# Main.net
KiCad netlist of a schematic drawn in Altium Designer
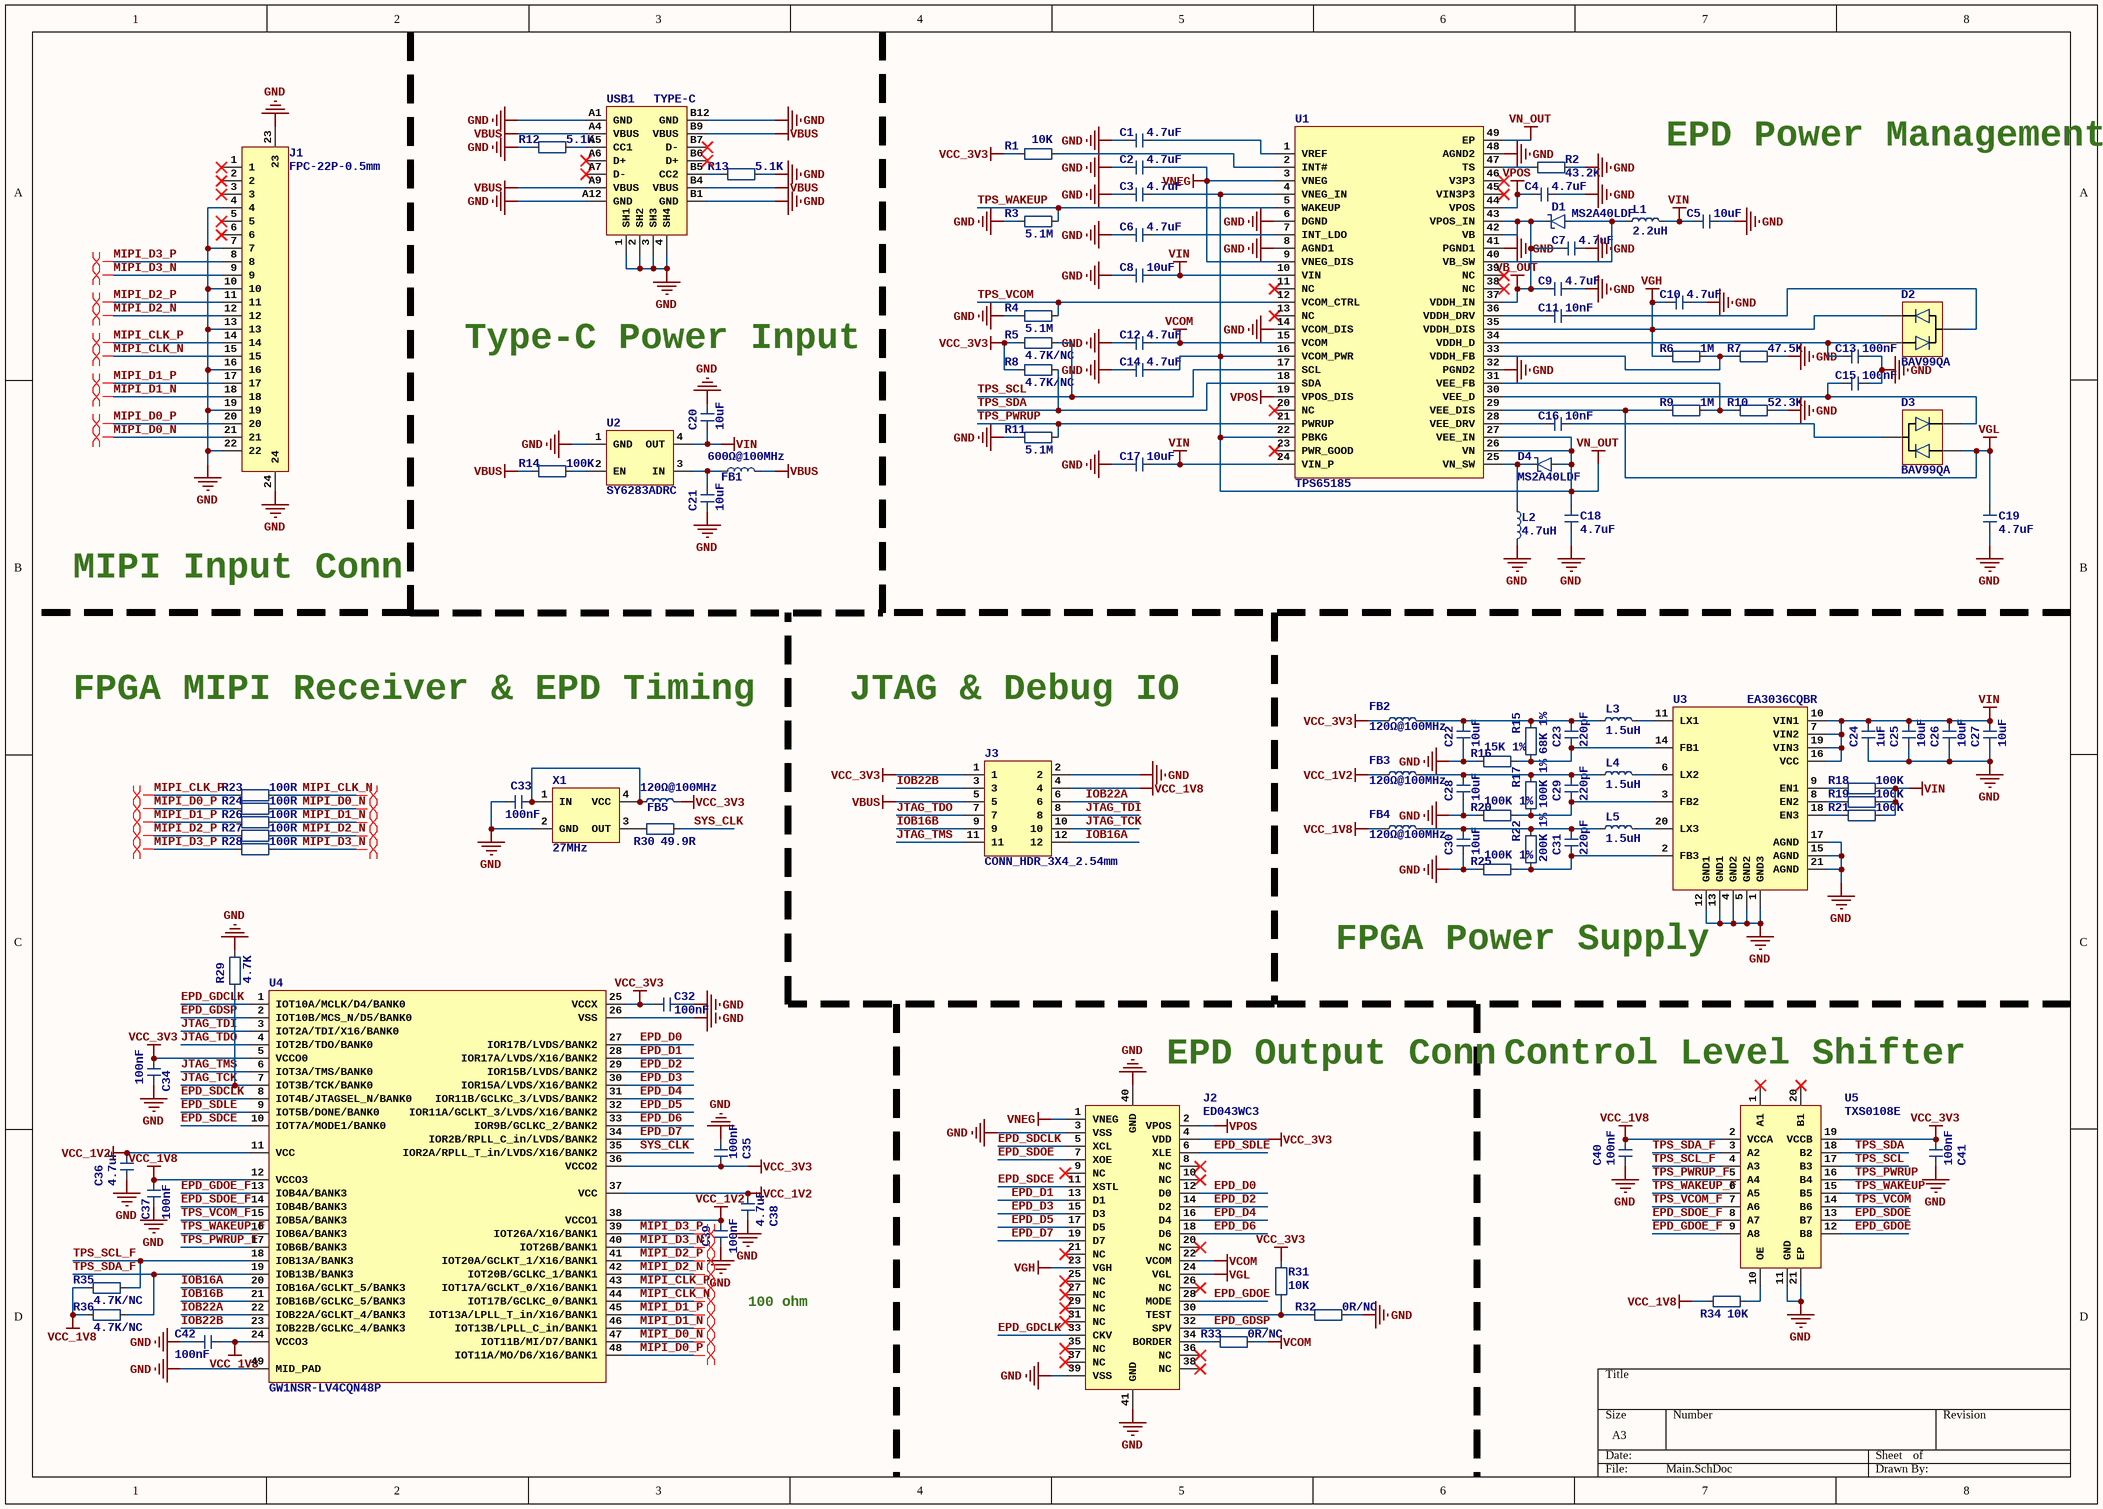
[diagram p0: Main.SchDoc]

(export (version "E")
  (design (tool "Eeschema 10.0.6"))
  (components
    (comp (ref "C1")
      (value "4.7uF")
      (footprint "Capacitor-0402")
      (description "CL05A475MO5NUNC")
      (libsource (lib "mLib") (part "Capacitor-0402"))
    )
    (comp (ref "C2")
      (value "4.7uF")
      (footprint "Capacitor-0805")
      (description "CL21A475KBQNNNE")
      (libsource (lib "mLib") (part "Capacitor-0805"))
    )
    (comp (ref "C3")
      (value "4.7uF")
      (footprint "Capacitor-0805")
      (description "CL21A475KBQNNNE")
      (libsource (lib "mLib") (part "Capacitor-0805"))
    )
    (comp (ref "C4")
      (value "4.7uF")
      (footprint "Capacitor-0805")
      (description "CL21A475KBQNNNE")
      (libsource (lib "mLib") (part "Capacitor-0805"))
    )
    (comp (ref "C5")
      (value "10uF")
      (footprint "Capacitor-0603")
      (description "CL10A106KP8NNNC")
      (libsource (lib "mLib") (part "Capacitor-0603"))
    )
    (comp (ref "C6")
      (value "4.7uF")
      (footprint "Capacitor-0402")
      (description "CL05A475MO5NUNC")
      (libsource (lib "mLib") (part "Capacitor-0402"))
    )
    (comp (ref "C7")
      (value "4.7uF")
      (footprint "Capacitor-0805")
      (description "CL21A475KBQNNNE")
      (libsource (lib "mLib") (part "Capacitor-0805"))
    )
    (comp (ref "C8")
      (value "10uF")
      (footprint "Capacitor-0603")
      (description "CL10A106KP8NNNC")
      (libsource (lib "mLib") (part "Capacitor-0603"))
    )
    (comp (ref "C9")
      (value "4.7uF")
      (footprint "Capacitor-0805")
      (description "CL21A475KBQNNNE")
      (libsource (lib "mLib") (part "Capacitor-0805"))
    )
    (comp (ref "C10")
      (value "4.7uF")
      (footprint "Capacitor-0805")
      (description "CL21A475KBQNNNE")
      (libsource (lib "mLib") (part "Capacitor-0805"))
    )
    (comp (ref "C11")
      (value "10nF")
      (footprint "Capacitor-0402")
      (description "CL05B103KB5NNNC")
      (libsource (lib "mLib") (part "Capacitor-0402"))
    )
    (comp (ref "C12")
      (value "4.7uF")
      (footprint "Capacitor-0402")
      (description "CL05A475MO5NUNC")
      (libsource (lib "mLib") (part "Capacitor-0402"))
    )
    (comp (ref "C13")
      (value "100nF")
      (footprint "Capacitor-0402")
      (description "0402B104K500NT")
      (libsource (lib "mLib") (part "Capacitor-0402"))
    )
    (comp (ref "C14")
      (value "4.7uF")
      (footprint "Capacitor-0805")
      (description "CL21A475KBQNNNE")
      (libsource (lib "mLib") (part "Capacitor-0805"))
    )
    (comp (ref "C15")
      (value "100nF")
      (footprint "Capacitor-0402")
      (description "0402B104K500NT")
      (libsource (lib "mLib") (part "Capacitor-0402"))
    )
    (comp (ref "C16")
      (value "10nF")
      (footprint "Capacitor-0402")
      (description "CL05B103KB5NNNC")
      (libsource (lib "mLib") (part "Capacitor-0402"))
    )
    (comp (ref "C17")
      (value "10uF")
      (footprint "Capacitor-0603")
      (description "CL10A106KP8NNNC")
      (libsource (lib "mLib") (part "Capacitor-0603"))
    )
    (comp (ref "C18")
      (value "4.7uF")
      (footprint "Capacitor-0805")
      (description "CL21A475KBQNNNE")
      (libsource (lib "mLib") (part "Capacitor-0805"))
    )
    (comp (ref "C19")
      (value "4.7uF")
      (footprint "Capacitor-0805")
      (description "CL21A475KBQNNNE")
      (libsource (lib "mLib") (part "Capacitor-0805"))
    )
    (comp (ref "C20")
      (value "10uF")
      (footprint "Capacitor-0402")
      (description "HGC0402R5106M100NTEJ")
      (libsource (lib "mLib") (part "Capacitor-0402"))
    )
    (comp (ref "C21")
      (value "10uF")
      (footprint "Capacitor-0402")
      (description "HGC0402R5106M100NTEJ")
      (libsource (lib "mLib") (part "Capacitor-0402"))
    )
    (comp (ref "C22")
      (value "10uF")
      (footprint "Capacitor-0402")
      (description "HGC0402R5106M100NTEJ")
      (libsource (lib "mLib") (part "Capacitor-0402"))
    )
    (comp (ref "C23")
      (value "220pF")
      (footprint "Capacitor-0402")
      (description "CL05C221JB5NNNC")
      (libsource (lib "mLib") (part "Capacitor-0402"))
    )
    (comp (ref "C24")
      (value "1uF")
      (footprint "Capacitor-0402")
      (description "CL05A105KO5NNNC")
      (libsource (lib "mLib") (part "Capacitor-0402"))
    )
    (comp (ref "C25")
      (value "10uF")
      (footprint "Capacitor-0402")
      (description "HGC0402R5106M100NTEJ")
      (libsource (lib "mLib") (part "Capacitor-0402"))
    )
    (comp (ref "C26")
      (value "10uF")
      (footprint "Capacitor-0402")
      (description "HGC0402R5106M100NTEJ")
      (libsource (lib "mLib") (part "Capacitor-0402"))
    )
    (comp (ref "C27")
      (value "10uF")
      (footprint "Capacitor-0402")
      (description "HGC0402R5106M100NTEJ")
      (libsource (lib "mLib") (part "Capacitor-0402"))
    )
    (comp (ref "C28")
      (value "10uF")
      (footprint "Capacitor-0402")
      (description "HGC0402R5106M100NTEJ")
      (libsource (lib "mLib") (part "Capacitor-0402"))
    )
    (comp (ref "C29")
      (value "220pF")
      (footprint "Capacitor-0402")
      (description "CL05C221JB5NNNC")
      (libsource (lib "mLib") (part "Capacitor-0402"))
    )
    (comp (ref "C30")
      (value "10uF")
      (footprint "Capacitor-0402")
      (description "HGC0402R5106M100NTEJ")
      (libsource (lib "mLib") (part "Capacitor-0402"))
    )
    (comp (ref "C31")
      (value "220pF")
      (footprint "Capacitor-0402")
      (description "CL05C221JB5NNNC")
      (libsource (lib "mLib") (part "Capacitor-0402"))
    )
    (comp (ref "C32")
      (value "100nF")
      (footprint "Capacitor-0402")
      (description "100nF/X5R/25V")
      (libsource (lib "mLib") (part "Capacitor-0402"))
    )
    (comp (ref "C33")
      (value "100nF")
      (footprint "Capacitor-0402")
      (description "100nF/X5R/25V")
      (libsource (lib "mLib") (part "Capacitor-0402"))
    )
    (comp (ref "C34")
      (value "100nF")
      (footprint "Capacitor-0402")
      (description "100nF/X5R/25V")
      (libsource (lib "mLib") (part "Capacitor-0402"))
    )
    (comp (ref "C35")
      (value "100nF")
      (footprint "Capacitor-0402")
      (description "100nF/X5R/25V")
      (libsource (lib "mLib") (part "Capacitor-0402"))
    )
    (comp (ref "C36")
      (value "4.7uF")
      (footprint "Capacitor-0402")
      (description "4.7uF/X5R/10V")
      (libsource (lib "mLib") (part "Capacitor-0402"))
    )
    (comp (ref "C37")
      (value "100nF")
      (footprint "Capacitor-0402")
      (description "100nF/X5R/25V")
      (libsource (lib "mLib") (part "Capacitor-0402"))
    )
    (comp (ref "C38")
      (value "4.7uF")
      (footprint "Capacitor-0402")
      (description "4.7uF/X5R/10V")
      (libsource (lib "mLib") (part "Capacitor-0402"))
    )
    (comp (ref "C39")
      (value "100nF")
      (footprint "Capacitor-0402")
      (description "100nF/X5R/25V")
      (libsource (lib "mLib") (part "Capacitor-0402"))
    )
    (comp (ref "C40")
      (value "100nF")
      (footprint "Capacitor-0402")
      (description "100nF/X5R/25V")
      (libsource (lib "mLib") (part "Capacitor-0402"))
    )
    (comp (ref "C41")
      (value "100nF")
      (footprint "Capacitor-0402")
      (description "100nF/X5R/25V")
      (libsource (lib "mLib") (part "Capacitor-0402"))
    )
    (comp (ref "C42")
      (value "100nF")
      (footprint "Capacitor-0402")
      (description "100nF/X5R/25V")
      (libsource (lib "mLib") (part "Capacitor-0402"))
    )
    (comp (ref "D1")
      (value "MS2A40LDF")
      (footprint "MS2A40LDF-DFN-2_1.6x1.0mm")
      (description "Schottky Diode-DFN-1610-2")
      (libsource (lib "mLib") (part "MS2A40LDF"))
    )
    (comp (ref "D2")
      (value "BAV99QA")
      (footprint "BAV99QA-DFN-3_1.1x1.0mm")
      (description "BAV99QA/1SS362FV")
      (libsource (lib "mLib") (part "BAV99QA"))
    )
    (comp (ref "D3")
      (value "BAV99QA")
      (footprint "BAV99QA-DFN-3_1.1x1.0mm")
      (description "BAV99QA/1SS362FV")
      (libsource (lib "") (part "BAV99QA_1"))
    )
    (comp (ref "D4")
      (value "MS2A40LDF")
      (footprint "MS2A40LDF-DFN-2_1.6x1.0mm")
      (description "Schottky Diode-DFN-1610-2")
      (libsource (lib "mLib") (part "MS2A40LDF"))
    )
    (comp (ref "FB1")
      (value "600Ω@100MHz")
      (footprint "Ferrite Bead-0603")
      (description "UPZ1608U601-1R3TF")
      (libsource (lib "mLib") (part "Ferrite Bead-0603"))
    )
    (comp (ref "FB2")
      (value "120Ω@100MHz")
      (footprint "Ferrite Bead-0402")
      (description "UPZ1005D121-1R3TF")
      (libsource (lib "mLib") (part "Ferrite Bead-0402"))
    )
    (comp (ref "FB3")
      (value "120Ω@100MHz")
      (footprint "Ferrite Bead-0402")
      (description "UPZ1005D121-1R3TF")
      (libsource (lib "mLib") (part "Ferrite Bead-0402"))
    )
    (comp (ref "FB4")
      (value "120Ω@100MHz")
      (footprint "Ferrite Bead-0402")
      (description "UPZ1005D121-1R3TF")
      (libsource (lib "mLib") (part "Ferrite Bead-0402"))
    )
    (comp (ref "FB5")
      (value "120Ω@100MHz")
      (footprint "Ferrite Bead-0402")
      (description "UPZ1005D121-1R3TF")
      (libsource (lib "mLib") (part "Ferrite Bead-0402"))
    )
    (comp (ref "J1")
      (value "FPC-22P-0.5mm")
      (footprint "HC-FPC-05-10-22RLTAG")
      (description "HC-FPC-05-10-22RLTAG")
      (libsource (lib "mLib") (part "FPC-22P-0.5mm"))
    )
    (comp (ref "J2")
      (value "ED043WC3")
      (footprint "ED043WC3")
      (description "AFE03-S39FMA-1H")
      (libsource (lib "mLib") (part "ED043WC3"))
    )
    (comp (ref "J3")
      (value "CONN_HDR_3X4_2.54mm")
      (footprint "CONN_HDR_3X4_2.54mm")
      (libsource (lib "mLib") (part "CONN_HDR_3X4_2.54mm"))
    )
    (comp (ref "L1")
      (value "2.2uH")
      (footprint "Inductor-2016")
      (description "FTC201612S2R2MBCA")
      (libsource (lib "mLib") (part "Inductor-2016"))
    )
    (comp (ref "L2")
      (value "4.7uH")
      (footprint "Inductor-2016")
      (description "FTC201610S4R7MBCA")
      (libsource (lib "mLib") (part "Inductor-2016"))
    )
    (comp (ref "L3")
      (value "1.5uH")
      (footprint "Inductor-2016")
      (description "FTC201610S1R5MBCA")
      (libsource (lib "mLib") (part "Inductor-2016"))
    )
    (comp (ref "L4")
      (value "1.5uH")
      (footprint "Inductor-2016")
      (description "FTC201610S1R5MBCA")
      (libsource (lib "mLib") (part "Inductor-2016"))
    )
    (comp (ref "L5")
      (value "1.5uH")
      (footprint "Inductor-2016")
      (description "FTC201610S1R5MBCA")
      (libsource (lib "mLib") (part "Inductor-2016"))
    )
    (comp (ref "R1")
      (value "10K")
      (footprint "Resistor-0402")
      (description "Resistor-0402")
      (libsource (lib "mLib") (part "Resistor-0402"))
    )
    (comp (ref "R2")
      (value "43.2K")
      (footprint "Resistor-0402")
      (description "Resistor-0402")
      (libsource (lib "mLib") (part "Resistor-0402"))
    )
    (comp (ref "R3")
      (value "5.1M")
      (footprint "Resistor-0402")
      (description "Resistor-0402")
      (libsource (lib "mLib") (part "Resistor-0402"))
    )
    (comp (ref "R4")
      (value "5.1M")
      (footprint "Resistor-0402")
      (description "Resistor-0402")
      (libsource (lib "mLib") (part "Resistor-0402"))
    )
    (comp (ref "R5")
      (value "4.7K/NC")
      (footprint "Resistor-0402")
      (description "Resistor-0402")
      (libsource (lib "mLib") (part "Resistor-0402"))
    )
    (comp (ref "R6")
      (value "1M")
      (footprint "Resistor-0402")
      (description "Resistor-0402")
      (libsource (lib "mLib") (part "Resistor-0402"))
    )
    (comp (ref "R7")
      (value "47.5K")
      (footprint "Resistor-0402")
      (description "Resistor-0402")
      (libsource (lib "mLib") (part "Resistor-0402"))
    )
    (comp (ref "R8")
      (value "4.7K/NC")
      (footprint "Resistor-0402")
      (description "Resistor-0402")
      (libsource (lib "mLib") (part "Resistor-0402"))
    )
    (comp (ref "R9")
      (value "1M")
      (footprint "Resistor-0402")
      (description "Resistor-0402")
      (libsource (lib "mLib") (part "Resistor-0402"))
    )
    (comp (ref "R10")
      (value "52.3K")
      (footprint "Resistor-0402")
      (description "Resistor-0402")
      (libsource (lib "mLib") (part "Resistor-0402"))
    )
    (comp (ref "R11")
      (value "5.1M")
      (footprint "Resistor-0402")
      (description "Resistor-0402")
      (libsource (lib "mLib") (part "Resistor-0402"))
    )
    (comp (ref "R12")
      (value "5.1K")
      (footprint "Resistor-0402")
      (description "Resistor-0402")
      (libsource (lib "mLib") (part "Resistor-0402"))
    )
    (comp (ref "R13")
      (value "5.1K")
      (footprint "Resistor-0402")
      (description "Resistor-0402")
      (libsource (lib "mLib") (part "Resistor-0402"))
    )
    (comp (ref "R14")
      (value "100K")
      (footprint "Resistor-0402")
      (description "Resistor-0402")
      (libsource (lib "mLib") (part "Resistor-0402"))
    )
    (comp (ref "R15")
      (value "68K 1%")
      (footprint "Resistor-0402")
      (description "Resistor-0402")
      (libsource (lib "mLib") (part "Resistor-0402"))
    )
    (comp (ref "R16")
      (value "15K 1%")
      (footprint "Resistor-0402")
      (description "Resistor-0402")
      (libsource (lib "mLib") (part "Resistor-0402"))
    )
    (comp (ref "R17")
      (value "100K 1%")
      (footprint "Resistor-0402")
      (description "Resistor-0402")
      (libsource (lib "mLib") (part "Resistor-0402"))
    )
    (comp (ref "R18")
      (value "100K")
      (footprint "Resistor-0402")
      (description "Resistor-0402")
      (libsource (lib "mLib") (part "Resistor-0402"))
    )
    (comp (ref "R19")
      (value "100K")
      (footprint "Resistor-0402")
      (description "Resistor-0402")
      (libsource (lib "mLib") (part "Resistor-0402"))
    )
    (comp (ref "R20")
      (value "100K 1%")
      (footprint "Resistor-0402")
      (description "Resistor-0402")
      (libsource (lib "mLib") (part "Resistor-0402"))
    )
    (comp (ref "R21")
      (value "100K")
      (footprint "Resistor-0402")
      (description "Resistor-0402")
      (libsource (lib "mLib") (part "Resistor-0402"))
    )
    (comp (ref "R22")
      (value "200K 1%")
      (footprint "Resistor-0402")
      (description "Resistor-0402")
      (libsource (lib "mLib") (part "Resistor-0402"))
    )
    (comp (ref "R23")
      (value "100R")
      (footprint "Resistor-0402")
      (description "Resistor-0402")
      (libsource (lib "mLib") (part "Resistor-0402"))
    )
    (comp (ref "R24")
      (value "100R")
      (footprint "Resistor-0402")
      (description "Resistor-0402")
      (libsource (lib "mLib") (part "Resistor-0402"))
    )
    (comp (ref "R25")
      (value "100K 1%")
      (footprint "Resistor-0402")
      (description "Resistor-0402")
      (libsource (lib "mLib") (part "Resistor-0402"))
    )
    (comp (ref "R26")
      (value "100R")
      (footprint "Resistor-0402")
      (description "Resistor-0402")
      (libsource (lib "mLib") (part "Resistor-0402"))
    )
    (comp (ref "R27")
      (value "100R")
      (footprint "Resistor-0402")
      (description "Resistor-0402")
      (libsource (lib "mLib") (part "Resistor-0402"))
    )
    (comp (ref "R28")
      (value "100R")
      (footprint "Resistor-0402")
      (description "Resistor-0402")
      (libsource (lib "mLib") (part "Resistor-0402"))
    )
    (comp (ref "R29")
      (value "4.7K")
      (footprint "Resistor-0402")
      (description "Resistor-0402")
      (libsource (lib "mLib") (part "Resistor-0402"))
    )
    (comp (ref "R30")
      (value "49.9R")
      (footprint "Resistor-0402")
      (description "Resistor-0402")
      (libsource (lib "mLib") (part "Resistor-0402"))
    )
    (comp (ref "R31")
      (value "10K")
      (footprint "Resistor-0402")
      (description "Resistor-0402")
      (libsource (lib "mLib") (part "Resistor-0402"))
    )
    (comp (ref "R32")
      (value "0R/NC")
      (footprint "Resistor-0402")
      (description "Resistor-0402")
      (libsource (lib "mLib") (part "Resistor-0402"))
    )
    (comp (ref "R33")
      (value "0R/NC")
      (footprint "Resistor-0402")
      (description "Resistor-0402")
      (libsource (lib "mLib") (part "Resistor-0402"))
    )
    (comp (ref "R34")
      (value "10K")
      (footprint "Resistor-0402")
      (description "Resistor-0402")
      (libsource (lib "mLib") (part "Resistor-0402"))
    )
    (comp (ref "R35")
      (value "4.7K/NC")
      (footprint "Resistor-0402")
      (description "Resistor-0402")
      (libsource (lib "mLib") (part "Resistor-0402"))
    )
    (comp (ref "R36")
      (value "4.7K/NC")
      (footprint "Resistor-0402")
      (description "Resistor-0402")
      (libsource (lib "mLib") (part "Resistor-0402"))
    )
    (comp (ref "U1")
      (value "TPS65185")
      (footprint "TPS65185-VQFN-48_6x6mm")
      (libsource (lib "mLib") (part "TPS65185"))
    )
    (comp (ref "U2")
      (value "SY6283ADRC")
      (footprint "SY6283ADRC-dfn-4_1.2x1.6mm")
      (libsource (lib "mLib") (part "SY6283ADRC"))
    )
    (comp (ref "U3")
      (value "EA3036CQBR")
      (footprint "EA3036-QFN-20")
      (description "QFN-20")
      (libsource (lib "mLib") (part "EA3036CQBR"))
    )
    (comp (ref "U4")
      (value "GW1NSR-LV4CQN48P")
      (footprint "GW1NSR-LV4CQN48P-QFN-48_6X6")
      (libsource (lib "mLib") (part "GW1NSR-LV4CQN48P"))
    )
    (comp (ref "U5")
      (value "TXS0108E")
      (footprint "TXS0108E-VQFN-20-3.5x4.5mm")
      (libsource (lib "mLib") (part "TXS0108E"))
    )
    (comp (ref "USB1")
      (value "TYPE-C")
      (footprint "TYPE-C-16P")
      (description "TYPE-C  16P")
      (libsource (lib "mLib") (part "TYPE-C"))
    )
    (comp (ref "X1")
      (value "27MHz")
      (footprint "Oscillator-2016")
      (description "SMD2016")
      (libsource (lib "mLib") (part "Oscillator_Source-2016"))
    )
  )
  (nets
    (net (code "1") (name "/EPD_D0") (class "Default")
      (node (ref "J2") (pin "12") (pinfunction "D0_12") (pintype "passive"))
      (node (ref "U4") (pin "27") (pinfunction "IOR17B/LVDS/BANK2_27") (pintype "passive"))
    )
    (net (code "2") (name "/EPD_D1") (class "Default")
      (node (ref "J2") (pin "13") (pinfunction "D1_13") (pintype "passive"))
      (node (ref "U4") (pin "28") (pinfunction "IOR17A/LVDS/X16/BANK2_28") (pintype "passive"))
    )
    (net (code "3") (name "/EPD_D2") (class "Default")
      (node (ref "J2") (pin "14") (pinfunction "D2_14") (pintype "passive"))
      (node (ref "U4") (pin "29") (pinfunction "IOR15B/LVDS/BANK2_29") (pintype "passive"))
    )
    (net (code "4") (name "/EPD_D3") (class "Default")
      (node (ref "J2") (pin "15") (pinfunction "D3_15") (pintype "passive"))
      (node (ref "U4") (pin "30") (pinfunction "IOR15A/LVDS/X16/BANK2_30") (pintype "passive"))
    )
    (net (code "5") (name "/EPD_D4") (class "Default")
      (node (ref "J2") (pin "16") (pinfunction "D4_16") (pintype "passive"))
      (node (ref "U4") (pin "31") (pinfunction "IOR11B/GCLKC_3/LVDS/BANK2_31") (pintype "passive"))
    )
    (net (code "6") (name "/EPD_D5") (class "Default")
      (node (ref "J2") (pin "17") (pinfunction "D5_17") (pintype "passive"))
      (node (ref "U4") (pin "32") (pinfunction "IOR11A/GCLKT_3/LVDS/X16/BANK2_32") (pintype "passive"))
    )
    (net (code "7") (name "/EPD_D6") (class "Default")
      (node (ref "J2") (pin "18") (pinfunction "D6_18") (pintype "passive"))
      (node (ref "U4") (pin "33") (pinfunction "IOR9B/GCLKC_2/BANK2_33") (pintype "passive"))
    )
    (net (code "8") (name "/EPD_D7") (class "Default")
      (node (ref "J2") (pin "19") (pinfunction "D7_19") (pintype "passive"))
      (node (ref "U4") (pin "34") (pinfunction "IOR2B/RPLL_C_in/LVDS/BANK2_34") (pintype "passive"))
    )
    (net (code "9") (name "/EPD_GDCLK") (class "Default")
      (node (ref "J2") (pin "33") (pinfunction "CKV_33") (pintype "passive"))
      (node (ref "U4") (pin "1") (pinfunction "IOT10A/MCLK/D4/BANK0_1") (pintype "passive"))
    )
    (net (code "10") (name "/EPD_GDOE") (class "Default")
      (node (ref "J2") (pin "28") (pinfunction "MODE_28") (pintype "passive"))
      (node (ref "U5") (pin "12") (pinfunction "B8_12") (pintype "passive"))
    )
    (net (code "11") (name "/EPD_GDOE_F") (class "Default")
      (node (ref "U4") (pin "13") (pinfunction "IOB4A/BANK3_13") (pintype "passive"))
      (node (ref "U5") (pin "9") (pinfunction "A8_9") (pintype "passive"))
    )
    (net (code "12") (name "/EPD_GDSP") (class "Default")
      (node (ref "J2") (pin "32") (pinfunction "SPV_32") (pintype "passive"))
      (node (ref "U4") (pin "2") (pinfunction "IOT10B/MCS_N/D5/BANK0_2") (pintype "passive"))
    )
    (net (code "13") (name "/EPD_SDCE") (class "Default")
      (node (ref "J2") (pin "11") (pinfunction "XSTL_11") (pintype "passive"))
      (node (ref "U4") (pin "10") (pinfunction "IOT7A/MODE1/BANK0_10") (pintype "passive"))
    )
    (net (code "14") (name "/EPD_SDCLK") (class "Default")
      (node (ref "J2") (pin "5") (pinfunction "XCL_5") (pintype "passive"))
      (node (ref "U4") (pin "8") (pinfunction "IOT4B/JTAGSEL_N/BANK0_8") (pintype "passive"))
    )
    (net (code "15") (name "/EPD_SDLE") (class "Default")
      (node (ref "J2") (pin "6") (pinfunction "XLE_6") (pintype "passive"))
      (node (ref "U4") (pin "9") (pinfunction "IOT5B/DONE/BANK0_9") (pintype "passive"))
    )
    (net (code "16") (name "/EPD_SDOE") (class "Default")
      (node (ref "J2") (pin "7") (pinfunction "XOE_7") (pintype "passive"))
      (node (ref "U5") (pin "13") (pinfunction "B7_13") (pintype "passive"))
    )
    (net (code "17") (name "/EPD_SDOE_F") (class "Default")
      (node (ref "U4") (pin "14") (pinfunction "IOB4B/BANK3_14") (pintype "passive"))
      (node (ref "U5") (pin "8") (pinfunction "A7_8") (pintype "passive"))
    )
    (net (code "18") (name "/IOB16A") (class "Default")
      (node (ref "J3") (pin "12") (pinfunction "12_12") (pintype "passive"))
      (node (ref "U4") (pin "20") (pinfunction "IOB16A/GCLKT_5/BANK3_20") (pintype "passive"))
    )
    (net (code "19") (name "/IOB16B") (class "Default")
      (node (ref "J3") (pin "9") (pinfunction "9_9") (pintype "passive"))
      (node (ref "U4") (pin "21") (pinfunction "IOB16B/GCLKC_5/BANK3_21") (pintype "passive"))
    )
    (net (code "20") (name "/IOB22A") (class "Default")
      (node (ref "J3") (pin "6") (pinfunction "6_6") (pintype "passive"))
      (node (ref "U4") (pin "22") (pinfunction "IOB22A/GCLKT_4/BANK3_22") (pintype "passive"))
    )
    (net (code "21") (name "/IOB22B") (class "Default")
      (node (ref "J3") (pin "3") (pinfunction "3_3") (pintype "passive"))
      (node (ref "U4") (pin "23") (pinfunction "IOB22B/GCLKC_4/BANK3_23") (pintype "passive"))
    )
    (net (code "22") (name "/JTAG_TCK") (class "Default")
      (node (ref "J3") (pin "10") (pinfunction "10_10") (pintype "passive"))
      (node (ref "R29") (pin "1") (pinfunction "1_1") (pintype "passive"))
      (node (ref "U4") (pin "7") (pinfunction "IOT3B/TCK/BANK0_7") (pintype "passive"))
    )
    (net (code "23") (name "/JTAG_TDI") (class "Default")
      (node (ref "J3") (pin "8") (pinfunction "8_8") (pintype "passive"))
      (node (ref "U4") (pin "3") (pinfunction "IOT2A/TDI/X16/BANK0_3") (pintype "passive"))
    )
    (net (code "24") (name "/JTAG_TDO") (class "Default")
      (node (ref "J3") (pin "7") (pinfunction "7_7") (pintype "passive"))
      (node (ref "U4") (pin "4") (pinfunction "IOT2B/TDO/BANK0_4") (pintype "passive"))
    )
    (net (code "25") (name "/JTAG_TMS") (class "Default")
      (node (ref "J3") (pin "11") (pinfunction "11_11") (pintype "passive"))
      (node (ref "U4") (pin "6") (pinfunction "IOT3A/TMS/BANK0_6") (pintype "passive"))
    )
    (net (code "26") (name "/MIPI_CLK_N") (class "Default")
      (node (ref "J1") (pin "15") (pinfunction "15_15") (pintype "passive"))
      (node (ref "R23") (pin "1") (pinfunction "1_1") (pintype "passive"))
      (node (ref "U4") (pin "44") (pinfunction "IOT17B/GCLKC_0/BANK1_44") (pintype "passive"))
    )
    (net (code "27") (name "/MIPI_CLK_P") (class "Default")
      (node (ref "J1") (pin "14") (pinfunction "14_14") (pintype "passive"))
      (node (ref "R23") (pin "2") (pinfunction "2_2") (pintype "passive"))
      (node (ref "U4") (pin "43") (pinfunction "IOT17A/GCLKT_0/X16/BANK1_43") (pintype "passive"))
    )
    (net (code "28") (name "/MIPI_D0_N") (class "Default")
      (node (ref "J1") (pin "21") (pinfunction "21_21") (pintype "passive"))
      (node (ref "R24") (pin "1") (pinfunction "1_1") (pintype "passive"))
      (node (ref "U4") (pin "47") (pinfunction "IOT11B/MI/D7/BANK1_47") (pintype "passive"))
    )
    (net (code "29") (name "/MIPI_D0_P") (class "Default")
      (node (ref "J1") (pin "20") (pinfunction "20_20") (pintype "passive"))
      (node (ref "R24") (pin "2") (pinfunction "2_2") (pintype "passive"))
      (node (ref "U4") (pin "48") (pinfunction "IOT11A/MO/D6/X16/BANK1_48") (pintype "passive"))
    )
    (net (code "30") (name "/MIPI_D1_N") (class "Default")
      (node (ref "J1") (pin "18") (pinfunction "18_18") (pintype "passive"))
      (node (ref "R26") (pin "1") (pinfunction "1_1") (pintype "passive"))
      (node (ref "U4") (pin "46") (pinfunction "IOT13B/LPLL_C_in/BANK1_46") (pintype "passive"))
    )
    (net (code "31") (name "/MIPI_D1_P") (class "Default")
      (node (ref "J1") (pin "17") (pinfunction "17_17") (pintype "passive"))
      (node (ref "R26") (pin "2") (pinfunction "2_2") (pintype "passive"))
      (node (ref "U4") (pin "45") (pinfunction "IOT13A/LPLL_T_in/X16/BANK1_45") (pintype "passive"))
    )
    (net (code "32") (name "/MIPI_D2_N") (class "Default")
      (node (ref "J1") (pin "12") (pinfunction "12_12") (pintype "passive"))
      (node (ref "R27") (pin "1") (pinfunction "1_1") (pintype "passive"))
      (node (ref "U4") (pin "42") (pinfunction "IOT20B/GCLKC_1/BANK1_42") (pintype "passive"))
    )
    (net (code "33") (name "/MIPI_D2_P") (class "Default")
      (node (ref "J1") (pin "11") (pinfunction "11_11") (pintype "passive"))
      (node (ref "R27") (pin "2") (pinfunction "2_2") (pintype "passive"))
      (node (ref "U4") (pin "41") (pinfunction "IOT20A/GCLKT_1/X16/BANK1_41") (pintype "passive"))
    )
    (net (code "34") (name "/MIPI_D3_N") (class "Default")
      (node (ref "J1") (pin "9") (pinfunction "9_9") (pintype "passive"))
      (node (ref "R28") (pin "1") (pinfunction "1_1") (pintype "passive"))
      (node (ref "U4") (pin "40") (pinfunction "IOT26B/BANK1_40") (pintype "passive"))
    )
    (net (code "35") (name "/MIPI_D3_P") (class "Default")
      (node (ref "J1") (pin "8") (pinfunction "8_8") (pintype "passive"))
      (node (ref "R28") (pin "2") (pinfunction "2_2") (pintype "passive"))
      (node (ref "U4") (pin "39") (pinfunction "IOT26A/X16/BANK1_39") (pintype "passive"))
    )
    (net (code "36") (name "/SYS_CLK") (class "Default")
      (node (ref "R30") (pin "1") (pinfunction "1_1") (pintype "passive"))
      (node (ref "U4") (pin "35") (pinfunction "IOR2A/RPLL_T_in/LVDS/X16/BANK2_35") (pintype "passive"))
    )
    (net (code "37") (name "/TPS_PWRUP") (class "Default")
      (node (ref "R11") (pin "1") (pinfunction "1_1") (pintype "passive"))
      (node (ref "U1") (pin "21") (pinfunction "PWRUP_21") (pintype "passive"))
      (node (ref "U5") (pin "16") (pinfunction "B4_16") (pintype "passive"))
    )
    (net (code "38") (name "/TPS_PWRUP_F") (class "Default")
      (node (ref "U4") (pin "17") (pinfunction "IOB6B/BANK3_17") (pintype "passive"))
      (node (ref "U5") (pin "5") (pinfunction "A4_5") (pintype "passive"))
    )
    (net (code "39") (name "/TPS_SCL") (class "Default")
      (node (ref "R5") (pin "1") (pinfunction "1_1") (pintype "passive"))
      (node (ref "U1") (pin "17") (pinfunction "SCL_17") (pintype "passive"))
      (node (ref "U5") (pin "17") (pinfunction "B3_17") (pintype "passive"))
    )
    (net (code "40") (name "/TPS_SCL_F") (class "Default")
      (node (ref "R35") (pin "1") (pinfunction "1_1") (pintype "passive"))
      (node (ref "U4") (pin "18") (pinfunction "IOB13A/BANK3_18") (pintype "passive"))
      (node (ref "U5") (pin "4") (pinfunction "A3_4") (pintype "passive"))
    )
    (net (code "41") (name "/TPS_SDA") (class "Default")
      (node (ref "R8") (pin "1") (pinfunction "1_1") (pintype "passive"))
      (node (ref "U1") (pin "18") (pinfunction "SDA_18") (pintype "passive"))
      (node (ref "U5") (pin "18") (pinfunction "B2_18") (pintype "passive"))
    )
    (net (code "42") (name "/TPS_SDA_F") (class "Default")
      (node (ref "R36") (pin "1") (pinfunction "1_1") (pintype "passive"))
      (node (ref "U4") (pin "19") (pinfunction "IOB13B/BANK3_19") (pintype "passive"))
      (node (ref "U5") (pin "3") (pinfunction "A2_3") (pintype "passive"))
    )
    (net (code "43") (name "/TPS_VCOM") (class "Default")
      (node (ref "R4") (pin "1") (pinfunction "1_1") (pintype "passive"))
      (node (ref "U1") (pin "12") (pinfunction "VCOM_CTRL_12") (pintype "passive"))
      (node (ref "U5") (pin "14") (pinfunction "B6_14") (pintype "passive"))
    )
    (net (code "44") (name "/TPS_VCOM_F") (class "Default")
      (node (ref "U4") (pin "15") (pinfunction "IOB5A/BANK3_15") (pintype "passive"))
      (node (ref "U5") (pin "7") (pinfunction "A6_7") (pintype "passive"))
    )
    (net (code "45") (name "/TPS_WAKEUP") (class "Default")
      (node (ref "R3") (pin "1") (pinfunction "1_1") (pintype "passive"))
      (node (ref "U1") (pin "5") (pinfunction "WAKEUP_5") (pintype "passive"))
      (node (ref "U5") (pin "15") (pinfunction "B5_15") (pintype "passive"))
    )
    (net (code "46") (name "/TPS_WAKEUP_F") (class "Default")
      (node (ref "U4") (pin "16") (pinfunction "IOB6A/BANK3_16") (pintype "passive"))
      (node (ref "U5") (pin "6") (pinfunction "A5_6") (pintype "passive"))
    )
    (net (code "47") (name "GND") (class "Default")
      (node (ref "C1") (pin "1") (pinfunction "1_1") (pintype "passive"))
      (node (ref "C10") (pin "2") (pinfunction "2_2") (pintype "passive"))
      (node (ref "C12") (pin "1") (pinfunction "1_1") (pintype "passive"))
      (node (ref "C13") (pin "2") (pinfunction "2_2") (pintype "passive"))
      (node (ref "C14") (pin "1") (pinfunction "1_1") (pintype "passive"))
      (node (ref "C15") (pin "2") (pinfunction "2_2") (pintype "passive"))
      (node (ref "C17") (pin "1") (pinfunction "1_1") (pintype "passive"))
      (node (ref "C18") (pin "1") (pinfunction "1_1") (pintype "passive"))
      (node (ref "C19") (pin "1") (pinfunction "1_1") (pintype "passive"))
      (node (ref "C2") (pin "1") (pinfunction "1_1") (pintype "passive"))
      (node (ref "C20") (pin "2") (pinfunction "2_2") (pintype "passive"))
      (node (ref "C21") (pin "1") (pinfunction "1_1") (pintype "passive"))
      (node (ref "C22") (pin "1") (pinfunction "1_1") (pintype "passive"))
      (node (ref "C24") (pin "1") (pinfunction "1_1") (pintype "passive"))
      (node (ref "C25") (pin "1") (pinfunction "1_1") (pintype "passive"))
      (node (ref "C26") (pin "1") (pinfunction "1_1") (pintype "passive"))
      (node (ref "C27") (pin "1") (pinfunction "1_1") (pintype "passive"))
      (node (ref "C28") (pin "1") (pinfunction "1_1") (pintype "passive"))
      (node (ref "C3") (pin "1") (pinfunction "1_1") (pintype "passive"))
      (node (ref "C30") (pin "1") (pinfunction "1_1") (pintype "passive"))
      (node (ref "C32") (pin "2") (pinfunction "2_2") (pintype "passive"))
      (node (ref "C33") (pin "2") (pinfunction "2_2") (pintype "passive"))
      (node (ref "C34") (pin "1") (pinfunction "1_1") (pintype "passive"))
      (node (ref "C35") (pin "2") (pinfunction "2_2") (pintype "passive"))
      (node (ref "C36") (pin "1") (pinfunction "1_1") (pintype "passive"))
      (node (ref "C37") (pin "1") (pinfunction "1_1") (pintype "passive"))
      (node (ref "C38") (pin "1") (pinfunction "1_1") (pintype "passive"))
      (node (ref "C39") (pin "1") (pinfunction "1_1") (pintype "passive"))
      (node (ref "C4") (pin "2") (pinfunction "2_2") (pintype "passive"))
      (node (ref "C40") (pin "1") (pinfunction "1_1") (pintype "passive"))
      (node (ref "C41") (pin "1") (pinfunction "1_1") (pintype "passive"))
      (node (ref "C42") (pin "2") (pinfunction "2_2") (pintype "passive"))
      (node (ref "C5") (pin "2") (pinfunction "2_2") (pintype "passive"))
      (node (ref "C6") (pin "1") (pinfunction "1_1") (pintype "passive"))
      (node (ref "C7") (pin "2") (pinfunction "2_2") (pintype "passive"))
      (node (ref "C8") (pin "1") (pinfunction "1_1") (pintype "passive"))
      (node (ref "C9") (pin "2") (pinfunction "2_2") (pintype "passive"))
      (node (ref "J1") (pin "10") (pinfunction "10_10") (pintype "passive"))
      (node (ref "J1") (pin "13") (pinfunction "13_13") (pintype "passive"))
      (node (ref "J1") (pin "16") (pinfunction "16_16") (pintype "passive"))
      (node (ref "J1") (pin "19") (pinfunction "19_19") (pintype "passive"))
      (node (ref "J1") (pin "22") (pinfunction "22_22") (pintype "passive"))
      (node (ref "J1") (pin "23") (pinfunction "23_23") (pintype "passive"))
      (node (ref "J1") (pin "24") (pinfunction "24_24") (pintype "passive"))
      (node (ref "J1") (pin "4") (pinfunction "4_4") (pintype "passive"))
      (node (ref "J1") (pin "7") (pinfunction "7_7") (pintype "passive"))
      (node (ref "J2") (pin "3") (pinfunction "VSS_3") (pintype "passive"))
      (node (ref "J2") (pin "39") (pinfunction "VSS_39") (pintype "passive"))
      (node (ref "J2") (pin "40") (pinfunction "GND_40") (pintype "passive"))
      (node (ref "J2") (pin "41") (pinfunction "GND_41") (pintype "passive"))
      (node (ref "J3") (pin "2") (pinfunction "2_2") (pintype "passive"))
      (node (ref "L2") (pin "2") (pinfunction "2_2") (pintype "passive"))
      (node (ref "R10") (pin "1") (pinfunction "1_1") (pintype "passive"))
      (node (ref "R11") (pin "2") (pinfunction "2_2") (pintype "passive"))
      (node (ref "R12") (pin "2") (pinfunction "2_2") (pintype "passive"))
      (node (ref "R13") (pin "1") (pinfunction "1_1") (pintype "passive"))
      (node (ref "R16") (pin "2") (pinfunction "2_2") (pintype "passive"))
      (node (ref "R2") (pin "1") (pinfunction "1_1") (pintype "passive"))
      (node (ref "R20") (pin "2") (pinfunction "2_2") (pintype "passive"))
      (node (ref "R25") (pin "2") (pinfunction "2_2") (pintype "passive"))
      (node (ref "R29") (pin "2") (pinfunction "2_2") (pintype "passive"))
      (node (ref "R3") (pin "2") (pinfunction "2_2") (pintype "passive"))
      (node (ref "R32") (pin "1") (pinfunction "1_1") (pintype "passive"))
      (node (ref "R4") (pin "2") (pinfunction "2_2") (pintype "passive"))
      (node (ref "R7") (pin "1") (pinfunction "1_1") (pintype "passive"))
      (node (ref "U1") (pin "14") (pinfunction "VCOM_DIS_14") (pintype "passive"))
      (node (ref "U1") (pin "32") (pinfunction "PGND2_32") (pintype "passive"))
      (node (ref "U1") (pin "41") (pinfunction "PGND1_41") (pintype "passive"))
      (node (ref "U1") (pin "48") (pinfunction "AGND2_48") (pintype "passive"))
      (node (ref "U1") (pin "6") (pinfunction "DGND_6") (pintype "passive"))
      (node (ref "U1") (pin "8") (pinfunction "AGND1_8") (pintype "passive"))
      (node (ref "U2") (pin "1") (pinfunction "GND_1") (pintype "passive"))
      (node (ref "U3") (pin "1") (pinfunction "GND3_1") (pintype "passive"))
      (node (ref "U3") (pin "12") (pinfunction "GND1_12") (pintype "passive"))
      (node (ref "U3") (pin "13") (pinfunction "GND1_13") (pintype "passive"))
      (node (ref "U3") (pin "15") (pinfunction "AGND_15") (pintype "passive"))
      (node (ref "U3") (pin "17") (pinfunction "AGND_17") (pintype "passive"))
      (node (ref "U3") (pin "21") (pinfunction "AGND_21") (pintype "passive"))
      (node (ref "U3") (pin "4") (pinfunction "GND2_4") (pintype "passive"))
      (node (ref "U3") (pin "5") (pinfunction "GND2_5") (pintype "passive"))
      (node (ref "U4") (pin "26") (pinfunction "VSS_26") (pintype "passive"))
      (node (ref "U4") (pin "49") (pinfunction "MID_PAD_49") (pintype "passive"))
      (node (ref "U5") (pin "11") (pinfunction "GND_11") (pintype "passive"))
      (node (ref "U5") (pin "21") (pinfunction "EP_21") (pintype "passive"))
      (node (ref "USB1") (pin "1") (pinfunction "SH1_1") (pintype "passive"))
      (node (ref "USB1") (pin "2") (pinfunction "SH2_2") (pintype "passive"))
      (node (ref "USB1") (pin "3") (pinfunction "SH3_3") (pintype "passive"))
      (node (ref "USB1") (pin "4") (pinfunction "SH4_4") (pintype "passive"))
      (node (ref "USB1") (pin "A1") (pinfunction "GND_A1") (pintype "passive"))
      (node (ref "USB1") (pin "A12") (pinfunction "GND_A12") (pintype "passive"))
      (node (ref "USB1") (pin "B1") (pinfunction "GND_B1") (pintype "passive"))
      (node (ref "USB1") (pin "B12") (pinfunction "GND_B12") (pintype "passive"))
      (node (ref "X1") (pin "2") (pinfunction "GND_2") (pintype "passive"))
    )
    (net (code "48") (name "Net-(C11-Pad2)") (class "Default")
      (node (ref "C11") (pin "2") (pinfunction "2_2") (pintype "passive"))
      (node (ref "D2") (pin "3") (pinfunction "3_3") (pintype "passive"))
    )
    (net (code "49") (name "Net-(C16-Pad2)") (class "Default")
      (node (ref "C16") (pin "2") (pinfunction "2_2") (pintype "passive"))
      (node (ref "D3") (pin "3") (pinfunction "3_3") (pintype "passive"))
    )
    (net (code "50") (name "Net-(C22-Pad2)") (class "Default")
      (node (ref "C22") (pin "2") (pinfunction "2_2") (pintype "passive"))
      (node (ref "C23") (pin "2") (pinfunction "2_2") (pintype "passive"))
      (node (ref "FB2") (pin "2") (pinfunction "2_2") (pintype "passive"))
      (node (ref "L3") (pin "1") (pinfunction "1_1") (pintype "passive"))
      (node (ref "R15") (pin "2") (pinfunction "2_2") (pintype "passive"))
    )
    (net (code "51") (name "Net-(C28-Pad2)") (class "Default")
      (node (ref "C28") (pin "2") (pinfunction "2_2") (pintype "passive"))
      (node (ref "C29") (pin "2") (pinfunction "2_2") (pintype "passive"))
      (node (ref "FB3") (pin "2") (pinfunction "2_2") (pintype "passive"))
      (node (ref "L4") (pin "1") (pinfunction "1_1") (pintype "passive"))
      (node (ref "R17") (pin "2") (pinfunction "2_2") (pintype "passive"))
    )
    (net (code "52") (name "Net-(C30-Pad2)") (class "Default")
      (node (ref "C30") (pin "2") (pinfunction "2_2") (pintype "passive"))
      (node (ref "C31") (pin "2") (pinfunction "2_2") (pintype "passive"))
      (node (ref "FB4") (pin "2") (pinfunction "2_2") (pintype "passive"))
      (node (ref "L5") (pin "1") (pinfunction "1_1") (pintype "passive"))
      (node (ref "R22") (pin "2") (pinfunction "2_2") (pintype "passive"))
    )
    (net (code "53") (name "Net-(J2-BORDER)") (class "Default")
      (node (ref "J2") (pin "34") (pinfunction "BORDER_34") (pintype "passive"))
      (node (ref "R33") (pin "2") (pinfunction "2_2") (pintype "passive"))
    )
    (net (code "54") (name "Net-(J2-TEST)") (class "Default")
      (node (ref "J2") (pin "30") (pinfunction "TEST_30") (pintype "passive"))
      (node (ref "R31") (pin "2") (pinfunction "2_2") (pintype "passive"))
      (node (ref "R32") (pin "2") (pinfunction "2_2") (pintype "passive"))
    )
    (net (code "55") (name "Net-(U1-INT#)") (class "Default")
      (node (ref "R1") (pin "1") (pinfunction "1_1") (pintype "passive"))
      (node (ref "U1") (pin "2") (pinfunction "INT#_2") (pintype "passive"))
    )
    (net (code "56") (name "Net-(U1-INT_LDO)") (class "Default")
      (node (ref "C6") (pin "2") (pinfunction "2_2") (pintype "passive"))
      (node (ref "U1") (pin "7") (pinfunction "INT_LDO_7") (pintype "passive"))
    )
    (net (code "57") (name "Net-(U1-TS)") (class "Default")
      (node (ref "R2") (pin "2") (pinfunction "2_2") (pintype "passive"))
      (node (ref "U1") (pin "47") (pinfunction "TS_47") (pintype "passive"))
    )
    (net (code "58") (name "Net-(U1-VB_SW)") (class "Default")
      (node (ref "D1") (pin "2") (pinfunction "2_2") (pintype "passive"))
      (node (ref "L1") (pin "1") (pinfunction "1_1") (pintype "passive"))
      (node (ref "U1") (pin "40") (pinfunction "VB_SW_40") (pintype "passive"))
    )
    (net (code "59") (name "Net-(U1-VDDH_D)") (class "Default")
      (node (ref "C13") (pin "1") (pinfunction "1_1") (pintype "passive"))
      (node (ref "D2") (pin "1") (pinfunction "1_1") (pintype "passive"))
      (node (ref "U1") (pin "34") (pinfunction "VDDH_D_34") (pintype "passive"))
    )
    (net (code "60") (name "Net-(U1-VDDH_DRV)") (class "Default")
      (node (ref "C11") (pin "1") (pinfunction "1_1") (pintype "passive"))
      (node (ref "U1") (pin "36") (pinfunction "VDDH_DRV_36") (pintype "passive"))
    )
    (net (code "61") (name "Net-(U1-VDDH_FB)") (class "Default")
      (node (ref "R6") (pin "1") (pinfunction "1_1") (pintype "passive"))
      (node (ref "R7") (pin "2") (pinfunction "2_2") (pintype "passive"))
      (node (ref "U1") (pin "33") (pinfunction "VDDH_FB_33") (pintype "passive"))
    )
    (net (code "62") (name "Net-(U1-VEE_D)") (class "Default")
      (node (ref "C15") (pin "1") (pinfunction "1_1") (pintype "passive"))
      (node (ref "D3") (pin "2") (pinfunction "2_2") (pintype "passive"))
      (node (ref "U1") (pin "30") (pinfunction "VEE_D_30") (pintype "passive"))
    )
    (net (code "63") (name "Net-(U1-VEE_DRV)") (class "Default")
      (node (ref "C16") (pin "1") (pinfunction "1_1") (pintype "passive"))
      (node (ref "U1") (pin "28") (pinfunction "VEE_DRV_28") (pintype "passive"))
    )
    (net (code "64") (name "Net-(U1-VEE_FB)") (class "Default")
      (node (ref "R10") (pin "2") (pinfunction "2_2") (pintype "passive"))
      (node (ref "R9") (pin "1") (pinfunction "1_1") (pintype "passive"))
      (node (ref "U1") (pin "31") (pinfunction "VEE_FB_31") (pintype "passive"))
    )
    (net (code "65") (name "Net-(U1-VN_SW)") (class "Default")
      (node (ref "D4") (pin "1") (pinfunction "1_1") (pintype "passive"))
      (node (ref "L2") (pin "1") (pinfunction "1_1") (pintype "passive"))
      (node (ref "U1") (pin "25") (pinfunction "VN_SW_25") (pintype "passive"))
    )
    (net (code "66") (name "Net-(U1-VREF)") (class "Default")
      (node (ref "C1") (pin "2") (pinfunction "2_2") (pintype "passive"))
      (node (ref "U1") (pin "1") (pinfunction "VREF_1") (pintype "passive"))
    )
    (net (code "67") (name "Net-(U2-EN)") (class "Default")
      (node (ref "R14") (pin "1") (pinfunction "1_1") (pintype "passive"))
      (node (ref "U2") (pin "2") (pinfunction "EN_2") (pintype "passive"))
    )
    (net (code "68") (name "Net-(U2-IN)") (class "Default")
      (node (ref "C21") (pin "2") (pinfunction "2_2") (pintype "passive"))
      (node (ref "FB1") (pin "1") (pinfunction "1_1") (pintype "passive"))
      (node (ref "U2") (pin "3") (pinfunction "IN_3") (pintype "passive"))
    )
    (net (code "69") (name "Net-(U3-EN1)") (class "Default")
      (node (ref "R18") (pin "2") (pinfunction "2_2") (pintype "passive"))
      (node (ref "U3") (pin "9") (pinfunction "EN1_9") (pintype "passive"))
    )
    (net (code "70") (name "Net-(U3-EN2)") (class "Default")
      (node (ref "R19") (pin "2") (pinfunction "2_2") (pintype "passive"))
      (node (ref "U3") (pin "8") (pinfunction "EN2_8") (pintype "passive"))
    )
    (net (code "71") (name "Net-(U3-EN3)") (class "Default")
      (node (ref "R21") (pin "2") (pinfunction "2_2") (pintype "passive"))
      (node (ref "U3") (pin "18") (pinfunction "EN3_18") (pintype "passive"))
    )
    (net (code "72") (name "Net-(U3-FB1)") (class "Default")
      (node (ref "C23") (pin "1") (pinfunction "1_1") (pintype "passive"))
      (node (ref "R15") (pin "1") (pinfunction "1_1") (pintype "passive"))
      (node (ref "R16") (pin "1") (pinfunction "1_1") (pintype "passive"))
      (node (ref "U3") (pin "14") (pinfunction "FB1_14") (pintype "passive"))
    )
    (net (code "73") (name "Net-(U3-FB2)") (class "Default")
      (node (ref "C29") (pin "1") (pinfunction "1_1") (pintype "passive"))
      (node (ref "R17") (pin "1") (pinfunction "1_1") (pintype "passive"))
      (node (ref "R20") (pin "1") (pinfunction "1_1") (pintype "passive"))
      (node (ref "U3") (pin "3") (pinfunction "FB2_3") (pintype "passive"))
    )
    (net (code "74") (name "Net-(U3-FB3)") (class "Default")
      (node (ref "C31") (pin "1") (pinfunction "1_1") (pintype "passive"))
      (node (ref "R22") (pin "1") (pinfunction "1_1") (pintype "passive"))
      (node (ref "R25") (pin "1") (pinfunction "1_1") (pintype "passive"))
      (node (ref "U3") (pin "2") (pinfunction "FB3_2") (pintype "passive"))
    )
    (net (code "75") (name "Net-(U3-LX1)") (class "Default")
      (node (ref "L3") (pin "2") (pinfunction "2_2") (pintype "passive"))
      (node (ref "U3") (pin "11") (pinfunction "LX1_11") (pintype "passive"))
    )
    (net (code "76") (name "Net-(U3-LX2)") (class "Default")
      (node (ref "L4") (pin "2") (pinfunction "2_2") (pintype "passive"))
      (node (ref "U3") (pin "6") (pinfunction "LX2_6") (pintype "passive"))
    )
    (net (code "77") (name "Net-(U3-LX3)") (class "Default")
      (node (ref "L5") (pin "2") (pinfunction "2_2") (pintype "passive"))
      (node (ref "U3") (pin "20") (pinfunction "LX3_20") (pintype "passive"))
    )
    (net (code "78") (name "Net-(U5-OE)") (class "Default")
      (node (ref "R34") (pin "1") (pinfunction "1_1") (pintype "passive"))
      (node (ref "U5") (pin "10") (pinfunction "OE_10") (pintype "passive"))
    )
    (net (code "79") (name "Net-(USB1-CC1)") (class "Default")
      (node (ref "R12") (pin "1") (pinfunction "1_1") (pintype "passive"))
      (node (ref "USB1") (pin "A5") (pinfunction "CC1_A5") (pintype "passive"))
    )
    (net (code "80") (name "Net-(USB1-CC2)") (class "Default")
      (node (ref "R13") (pin "2") (pinfunction "2_2") (pintype "passive"))
      (node (ref "USB1") (pin "B5") (pinfunction "CC2_B5") (pintype "passive"))
    )
    (net (code "81") (name "Net-(X1-IN)") (class "Default")
      (node (ref "C33") (pin "1") (pinfunction "1_1") (pintype "passive"))
      (node (ref "FB5") (pin "1") (pinfunction "1_1") (pintype "passive"))
      (node (ref "X1") (pin "1") (pinfunction "IN_1") (pintype "passive"))
      (node (ref "X1") (pin "4") (pinfunction "VCC_4") (pintype "passive"))
    )
    (net (code "82") (name "Net-(X1-OUT)") (class "Default")
      (node (ref "R30") (pin "2") (pinfunction "2_2") (pintype "passive"))
      (node (ref "X1") (pin "3") (pinfunction "OUT_3") (pintype "passive"))
    )
    (net (code "83") (name "VBUS") (class "Default")
      (node (ref "FB1") (pin "2") (pinfunction "2_2") (pintype "passive"))
      (node (ref "J3") (pin "5") (pinfunction "5_5") (pintype "passive"))
      (node (ref "R14") (pin "2") (pinfunction "2_2") (pintype "passive"))
      (node (ref "USB1") (pin "A4") (pinfunction "VBUS_A4") (pintype "passive"))
      (node (ref "USB1") (pin "A9") (pinfunction "VBUS_A9") (pintype "passive"))
      (node (ref "USB1") (pin "B4") (pinfunction "VBUS_B4") (pintype "passive"))
      (node (ref "USB1") (pin "B9") (pinfunction "VBUS_B9") (pintype "passive"))
    )
    (net (code "84") (name "VB_OUT") (class "Default")
      (node (ref "C7") (pin "1") (pinfunction "1_1") (pintype "passive"))
      (node (ref "C9") (pin "1") (pinfunction "1_1") (pintype "passive"))
      (node (ref "D1") (pin "1") (pinfunction "1_1") (pintype "passive"))
      (node (ref "U1") (pin "37") (pinfunction "VDDH_IN_37") (pintype "passive"))
      (node (ref "U1") (pin "42") (pinfunction "VB_42") (pintype "passive"))
      (node (ref "U1") (pin "43") (pinfunction "VPOS_IN_43") (pintype "passive"))
    )
    (net (code "85") (name "VCC_1V2") (class "Default")
      (node (ref "C36") (pin "2") (pinfunction "2_2") (pintype "passive"))
      (node (ref "C38") (pin "2") (pinfunction "2_2") (pintype "passive"))
      (node (ref "C39") (pin "2") (pinfunction "2_2") (pintype "passive"))
      (node (ref "FB3") (pin "1") (pinfunction "1_1") (pintype "passive"))
      (node (ref "U4") (pin "11") (pinfunction "VCC_11") (pintype "passive"))
      (node (ref "U4") (pin "37") (pinfunction "VCC_37") (pintype "passive"))
      (node (ref "U4") (pin "38") (pinfunction "VCCO1_38") (pintype "passive"))
    )
    (net (code "86") (name "VCC_1V8") (class "Default")
      (node (ref "C37") (pin "2") (pinfunction "2_2") (pintype "passive"))
      (node (ref "C40") (pin "2") (pinfunction "2_2") (pintype "passive"))
      (node (ref "C42") (pin "1") (pinfunction "1_1") (pintype "passive"))
      (node (ref "FB4") (pin "1") (pinfunction "1_1") (pintype "passive"))
      (node (ref "J3") (pin "4") (pinfunction "4_4") (pintype "passive"))
      (node (ref "R34") (pin "2") (pinfunction "2_2") (pintype "passive"))
      (node (ref "R35") (pin "2") (pinfunction "2_2") (pintype "passive"))
      (node (ref "R36") (pin "2") (pinfunction "2_2") (pintype "passive"))
      (node (ref "U4") (pin "12") (pinfunction "VCCO3_12") (pintype "passive"))
      (node (ref "U4") (pin "24") (pinfunction "VCCO3_24") (pintype "passive"))
      (node (ref "U5") (pin "2") (pinfunction "VCCA_2") (pintype "passive"))
    )
    (net (code "87") (name "VCC_3V3") (class "Default")
      (node (ref "C32") (pin "1") (pinfunction "1_1") (pintype "passive"))
      (node (ref "C34") (pin "2") (pinfunction "2_2") (pintype "passive"))
      (node (ref "C35") (pin "1") (pinfunction "1_1") (pintype "passive"))
      (node (ref "C41") (pin "2") (pinfunction "2_2") (pintype "passive"))
      (node (ref "FB2") (pin "1") (pinfunction "1_1") (pintype "passive"))
      (node (ref "FB5") (pin "2") (pinfunction "2_2") (pintype "passive"))
      (node (ref "J2") (pin "4") (pinfunction "VDD_4") (pintype "passive"))
      (node (ref "J3") (pin "1") (pinfunction "1_1") (pintype "passive"))
      (node (ref "R1") (pin "2") (pinfunction "2_2") (pintype "passive"))
      (node (ref "R31") (pin "1") (pinfunction "1_1") (pintype "passive"))
      (node (ref "R5") (pin "2") (pinfunction "2_2") (pintype "passive"))
      (node (ref "R8") (pin "2") (pinfunction "2_2") (pintype "passive"))
      (node (ref "U4") (pin "25") (pinfunction "VCCX_25") (pintype "passive"))
      (node (ref "U4") (pin "36") (pinfunction "VCCO2_36") (pintype "passive"))
      (node (ref "U4") (pin "5") (pinfunction "VCCO0_5") (pintype "passive"))
      (node (ref "U5") (pin "19") (pinfunction "VCCB_19") (pintype "passive"))
    )
    (net (code "88") (name "VCOM") (class "Default")
      (node (ref "C12") (pin "2") (pinfunction "2_2") (pintype "passive"))
      (node (ref "J2") (pin "22") (pinfunction "VCOM_22") (pintype "passive"))
      (node (ref "R33") (pin "1") (pinfunction "1_1") (pintype "passive"))
      (node (ref "U1") (pin "15") (pinfunction "VCOM_15") (pintype "passive"))
    )
    (net (code "89") (name "VGH") (class "Default")
      (node (ref "C10") (pin "1") (pinfunction "1_1") (pintype "passive"))
      (node (ref "D2") (pin "2") (pinfunction "2_2") (pintype "passive"))
      (node (ref "J2") (pin "23") (pinfunction "VGH_23") (pintype "passive"))
      (node (ref "R6") (pin "2") (pinfunction "2_2") (pintype "passive"))
      (node (ref "U1") (pin "35") (pinfunction "VDDH_DIS_35") (pintype "passive"))
    )
    (net (code "90") (name "VGL") (class "Default")
      (node (ref "C19") (pin "2") (pinfunction "2_2") (pintype "passive"))
      (node (ref "D3") (pin "1") (pinfunction "1_1") (pintype "passive"))
      (node (ref "J2") (pin "24") (pinfunction "VGL_24") (pintype "passive"))
      (node (ref "R9") (pin "2") (pinfunction "2_2") (pintype "passive"))
      (node (ref "U1") (pin "29") (pinfunction "VEE_DIS_29") (pintype "passive"))
    )
    (net (code "91") (name "VIN") (class "Default")
      (node (ref "C17") (pin "2") (pinfunction "2_2") (pintype "passive"))
      (node (ref "C20") (pin "1") (pinfunction "1_1") (pintype "passive"))
      (node (ref "C24") (pin "2") (pinfunction "2_2") (pintype "passive"))
      (node (ref "C25") (pin "2") (pinfunction "2_2") (pintype "passive"))
      (node (ref "C26") (pin "2") (pinfunction "2_2") (pintype "passive"))
      (node (ref "C27") (pin "2") (pinfunction "2_2") (pintype "passive"))
      (node (ref "C5") (pin "1") (pinfunction "1_1") (pintype "passive"))
      (node (ref "C8") (pin "2") (pinfunction "2_2") (pintype "passive"))
      (node (ref "L1") (pin "2") (pinfunction "2_2") (pintype "passive"))
      (node (ref "R18") (pin "1") (pinfunction "1_1") (pintype "passive"))
      (node (ref "R19") (pin "1") (pinfunction "1_1") (pintype "passive"))
      (node (ref "R21") (pin "1") (pinfunction "1_1") (pintype "passive"))
      (node (ref "U1") (pin "10") (pinfunction "VIN_10") (pintype "passive"))
      (node (ref "U1") (pin "24") (pinfunction "VIN_P_24") (pintype "passive"))
      (node (ref "U2") (pin "4") (pinfunction "OUT_4") (pintype "passive"))
      (node (ref "U3") (pin "10") (pinfunction "VIN1_10") (pintype "passive"))
      (node (ref "U3") (pin "16") (pinfunction "VCC_16") (pintype "passive"))
      (node (ref "U3") (pin "19") (pinfunction "VIN3_19") (pintype "passive"))
      (node (ref "U3") (pin "7") (pinfunction "VIN2_7") (pintype "passive"))
    )
    (net (code "92") (name "VNEG") (class "Default")
      (node (ref "C2") (pin "2") (pinfunction "2_2") (pintype "passive"))
      (node (ref "J2") (pin "1") (pinfunction "VNEG_1") (pintype "passive"))
      (node (ref "U1") (pin "3") (pinfunction "VNEG_3") (pintype "passive"))
      (node (ref "U1") (pin "9") (pinfunction "VNEG_DIS_9") (pintype "passive"))
    )
    (net (code "93") (name "VN_OUT") (class "Default")
      (node (ref "C14") (pin "2") (pinfunction "2_2") (pintype "passive"))
      (node (ref "C18") (pin "2") (pinfunction "2_2") (pintype "passive"))
      (node (ref "C3") (pin "2") (pinfunction "2_2") (pintype "passive"))
      (node (ref "D4") (pin "2") (pinfunction "2_2") (pintype "passive"))
      (node (ref "U1") (pin "16") (pinfunction "VCOM_PWR_16") (pintype "passive"))
      (node (ref "U1") (pin "22") (pinfunction "PBKG_22") (pintype "passive"))
      (node (ref "U1") (pin "26") (pinfunction "VN_26") (pintype "passive"))
      (node (ref "U1") (pin "27") (pinfunction "VEE_IN_27") (pintype "passive"))
      (node (ref "U1") (pin "4") (pinfunction "VNEG_IN_4") (pintype "passive"))
      (node (ref "U1") (pin "49") (pinfunction "EP_49") (pintype "passive"))
    )
    (net (code "94") (name "VPOS") (class "Default")
      (node (ref "C4") (pin "1") (pinfunction "1_1") (pintype "passive"))
      (node (ref "J2") (pin "2") (pinfunction "VPOS_2") (pintype "passive"))
      (node (ref "U1") (pin "19") (pinfunction "VPOS_DIS_19") (pintype "passive"))
      (node (ref "U1") (pin "44") (pinfunction "VPOS_44") (pintype "passive"))
    )
    (net (code "95") (name "unconnected-(J1-Pad1)") (class "Default")
      (node (ref "J1") (pin "1") (pinfunction "1_1") (pintype "passive+no_connect"))
    )
    (net (code "96") (name "unconnected-(J1-Pad2)") (class "Default")
      (node (ref "J1") (pin "2") (pinfunction "2_2") (pintype "passive+no_connect"))
    )
    (net (code "97") (name "unconnected-(J1-Pad3)") (class "Default")
      (node (ref "J1") (pin "3") (pinfunction "3_3") (pintype "passive+no_connect"))
    )
    (net (code "98") (name "unconnected-(J1-Pad5)") (class "Default")
      (node (ref "J1") (pin "5") (pinfunction "5_5") (pintype "passive+no_connect"))
    )
    (net (code "99") (name "unconnected-(J1-Pad6)") (class "Default")
      (node (ref "J1") (pin "6") (pinfunction "6_6") (pintype "passive+no_connect"))
    )
    (net (code "100") (name "unconnected-(J2-NC-Pad8)") (class "Default")
      (node (ref "J2") (pin "8") (pinfunction "NC_8") (pintype "passive+no_connect"))
    )
    (net (code "101") (name "unconnected-(J2-NC-Pad9)") (class "Default")
      (node (ref "J2") (pin "9") (pinfunction "NC_9") (pintype "passive+no_connect"))
    )
    (net (code "102") (name "unconnected-(J2-NC-Pad10)") (class "Default")
      (node (ref "J2") (pin "10") (pinfunction "NC_10") (pintype "passive+no_connect"))
    )
    (net (code "103") (name "unconnected-(J2-NC-Pad20)") (class "Default")
      (node (ref "J2") (pin "20") (pinfunction "NC_20") (pintype "passive+no_connect"))
    )
    (net (code "104") (name "unconnected-(J2-NC-Pad21)") (class "Default")
      (node (ref "J2") (pin "21") (pinfunction "NC_21") (pintype "passive+no_connect"))
    )
    (net (code "105") (name "unconnected-(J2-NC-Pad25)") (class "Default")
      (node (ref "J2") (pin "25") (pinfunction "NC_25") (pintype "passive+no_connect"))
    )
    (net (code "106") (name "unconnected-(J2-NC-Pad26)") (class "Default")
      (node (ref "J2") (pin "26") (pinfunction "NC_26") (pintype "passive+no_connect"))
    )
    (net (code "107") (name "unconnected-(J2-NC-Pad27)") (class "Default")
      (node (ref "J2") (pin "27") (pinfunction "NC_27") (pintype "passive+no_connect"))
    )
    (net (code "108") (name "unconnected-(J2-NC-Pad29)") (class "Default")
      (node (ref "J2") (pin "29") (pinfunction "NC_29") (pintype "passive+no_connect"))
    )
    (net (code "109") (name "unconnected-(J2-NC-Pad31)") (class "Default")
      (node (ref "J2") (pin "31") (pinfunction "NC_31") (pintype "passive+no_connect"))
    )
    (net (code "110") (name "unconnected-(J2-NC-Pad35)") (class "Default")
      (node (ref "J2") (pin "35") (pinfunction "NC_35") (pintype "passive+no_connect"))
    )
    (net (code "111") (name "unconnected-(J2-NC-Pad36)") (class "Default")
      (node (ref "J2") (pin "36") (pinfunction "NC_36") (pintype "passive+no_connect"))
    )
    (net (code "112") (name "unconnected-(J2-NC-Pad37)") (class "Default")
      (node (ref "J2") (pin "37") (pinfunction "NC_37") (pintype "passive+no_connect"))
    )
    (net (code "113") (name "unconnected-(J2-NC-Pad38)") (class "Default")
      (node (ref "J2") (pin "38") (pinfunction "NC_38") (pintype "passive+no_connect"))
    )
    (net (code "114") (name "unconnected-(U1-NC-Pad11)") (class "Default")
      (node (ref "U1") (pin "11") (pinfunction "NC_11") (pintype "passive+no_connect"))
    )
    (net (code "115") (name "unconnected-(U1-NC-Pad13)") (class "Default")
      (node (ref "U1") (pin "13") (pinfunction "NC_13") (pintype "passive+no_connect"))
    )
    (net (code "116") (name "unconnected-(U1-NC-Pad20)") (class "Default")
      (node (ref "U1") (pin "20") (pinfunction "NC_20") (pintype "passive+no_connect"))
    )
    (net (code "117") (name "unconnected-(U1-NC-Pad38)") (class "Default")
      (node (ref "U1") (pin "38") (pinfunction "NC_38") (pintype "passive+no_connect"))
    )
    (net (code "118") (name "unconnected-(U1-NC-Pad39)") (class "Default")
      (node (ref "U1") (pin "39") (pinfunction "NC_39") (pintype "passive+no_connect"))
    )
    (net (code "119") (name "unconnected-(U1-PWR_GOOD-Pad23)") (class "Default")
      (node (ref "U1") (pin "23") (pinfunction "PWR_GOOD_23") (pintype "passive+no_connect"))
    )
    (net (code "120") (name "unconnected-(U1-V3P3-Pad46)") (class "Default")
      (node (ref "U1") (pin "46") (pinfunction "V3P3_46") (pintype "passive+no_connect"))
    )
    (net (code "121") (name "unconnected-(U1-VIN3P3-Pad45)") (class "Default")
      (node (ref "U1") (pin "45") (pinfunction "VIN3P3_45") (pintype "passive+no_connect"))
    )
    (net (code "122") (name "unconnected-(U5-A1-Pad1)") (class "Default")
      (node (ref "U5") (pin "1") (pinfunction "A1_1") (pintype "passive+no_connect"))
    )
    (net (code "123") (name "unconnected-(U5-B1-Pad20)") (class "Default")
      (node (ref "U5") (pin "20") (pinfunction "B1_20") (pintype "passive+no_connect"))
    )
    (net (code "124") (name "unconnected-(USB1-D+-PadA6)") (class "Default")
      (node (ref "USB1") (pin "A6") (pinfunction "D+_A6") (pintype "passive+no_connect"))
    )
    (net (code "125") (name "unconnected-(USB1-D+-PadB6)") (class "Default")
      (node (ref "USB1") (pin "B6") (pinfunction "D+_B6") (pintype "passive+no_connect"))
    )
    (net (code "126") (name "unconnected-(USB1-D--PadA7)") (class "Default")
      (node (ref "USB1") (pin "A7") (pinfunction "D-_A7") (pintype "passive+no_connect"))
    )
    (net (code "127") (name "unconnected-(USB1-D--PadB7)") (class "Default")
      (node (ref "USB1") (pin "B7") (pinfunction "D-_B7") (pintype "passive+no_connect"))
    )
  )
)
